# Glenn.net
KiCad netlist of a schematic drawn in Altium Designer
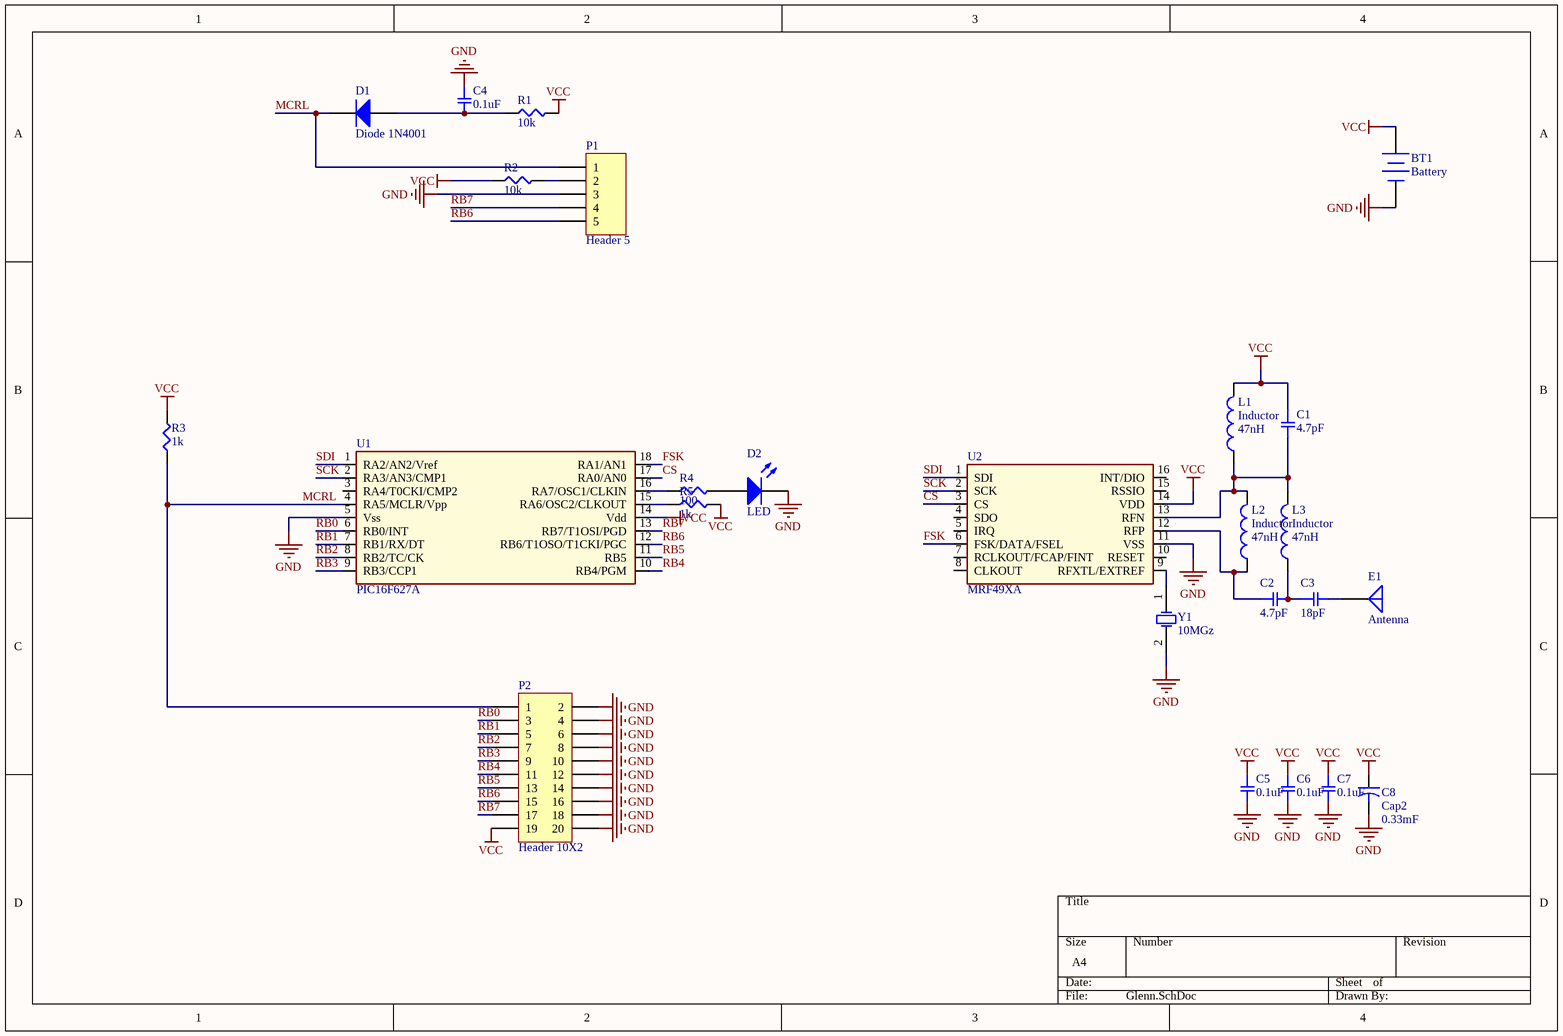
[diagram p0: Glenn.SchDoc]

(export (version "E")
  (design (tool "Eeschema 10.0.6"))
  (components
    (comp (ref "BT1")
      (value "Battery")
      (footprint "BAT-2")
      (description "Multicell Battery")
      (fields (field (name "PUBLISHER") "Altium Limited"))
      (libsource (lib "Miscellaneous Devices") (part "Battery"))
    )
    (comp (ref "C1")
      (value "4.7pF")
      (footprint "SMD-1206C")
      (description "CAP CER 0.033UF 250V X7T 1206")
      (fields
        (field (name "DIGI-KEY PART NUMBER") "490-13989-1-ND")
        (field (name "PART NUMBER") "GC331AD72E333KX01D")
      )
      (libsource (lib "capacitor_murata_1206") (part "GC331AD72E333KX01D"))
    )
    (comp (ref "C2")
      (value "4.7pF")
      (footprint "SMD-1206C")
      (description "CAP CER 0.033UF 250V X7T 1206")
      (fields
        (field (name "DIGI-KEY PART NUMBER") "490-13989-1-ND")
        (field (name "PART NUMBER") "GC331AD72E333KX01D")
      )
      (libsource (lib "capacitor_murata_1206") (part "GC331AD72E333KX01D"))
    )
    (comp (ref "C3")
      (value "18pF")
      (footprint "SMD-1206C")
      (description "CAP CER 0.033UF 250V X7T 1206")
      (fields
        (field (name "DIGI-KEY PART NUMBER") "490-13989-1-ND")
        (field (name "PART NUMBER") "GC331AD72E333KX01D")
      )
      (libsource (lib "capacitor_murata_1206") (part "GC331AD72E333KX01D"))
    )
    (comp (ref "C4")
      (value "0.1uF")
      (footprint "SMD-0805C")
      (description "CAP CER 10000PF 250V X7T 0805")
      (fields
        (field (name "DIGI-KEY PART NUMBER") "490-13986-1-ND")
        (field (name "PART NUMBER") "GC321AD72E103KX01D")
      )
      (libsource (lib "capacitor_murata_0805") (part "GC321AD72E103KX01D"))
    )
    (comp (ref "C5")
      (value "0.1uF")
      (footprint "SMD-0805C")
      (description "CAP CER 10000PF 250V X7T 0805")
      (fields
        (field (name "DIGI-KEY PART NUMBER") "490-13986-1-ND")
        (field (name "PART NUMBER") "GC321AD72E103KX01D")
      )
      (libsource (lib "capacitor_murata_0805") (part "GC321AD72E103KX01D"))
    )
    (comp (ref "C6")
      (value "0.1uF")
      (footprint "SMD-0805C")
      (description "CAP CER 10000PF 250V X7T 0805")
      (fields
        (field (name "DIGI-KEY PART NUMBER") "490-13986-1-ND")
        (field (name "PART NUMBER") "GC321AD72E103KX01D")
      )
      (libsource (lib "capacitor_murata_0805") (part "GC321AD72E103KX01D"))
    )
    (comp (ref "C7")
      (value "0.1uF")
      (footprint "SMD-0805C")
      (description "CAP CER 10000PF 250V X7T 0805")
      (fields
        (field (name "DIGI-KEY PART NUMBER") "490-13986-1-ND")
        (field (name "PART NUMBER") "GC321AD72E103KX01D")
      )
      (libsource (lib "capacitor_murata_0805") (part "GC321AD72E103KX01D"))
    )
    (comp (ref "C8")
      (value "Cap2")
      (footprint "CAPR5-4X5")
      (description "Capacitor")
      (fields (field (name "ALTIUM_VALUE") "0.33mF") (field (name "PUBLISHER") "Altium Limited"))
      (libsource (lib "Miscellaneous Devices") (part "Cap2"))
    )
    (comp (ref "D1")
      (value "Diode 1N4001")
      (footprint "DO-41")
      (description "1 Amp General Purpose Rectifier")
      (fields (field (name "PUBLISHER") "Altium Limited"))
      (libsource (lib "Miscellaneous Devices") (part "Diode 1N4001"))
    )
    (comp (ref "D2")
      (value "LED")
      (footprint "3.5X2.8X1.9")
      (description "Typical BLUE SiC LED")
      (fields (field (name "PUBLISHER") "Altium Limited"))
      (libsource (lib "Miscellaneous Devices") (part "LED3"))
    )
    (comp (ref "E1")
      (value "Antenna")
      (footprint "PIN1")
      (description "Generic Antenna")
      (fields (field (name "PUBLISHER") "Altium Limited"))
      (libsource (lib "Miscellaneous Devices") (part "Antenna"))
    )
    (comp (ref "L1")
      (value "Inductor")
      (footprint "0402-A")
      (fields (field (name "ALTIUM_VALUE") "47nH") (field (name "PUBLISHER") "Altium Limited"))
      (libsource (lib "Miscellaneous Devices") (part "Inductor"))
    )
    (comp (ref "L2")
      (value "Inductor")
      (footprint "0402-A")
      (fields (field (name "ALTIUM_VALUE") "47nH") (field (name "PUBLISHER") "Altium Limited"))
      (libsource (lib "Miscellaneous Devices") (part "Inductor"))
    )
    (comp (ref "L3")
      (value "Inductor")
      (footprint "0402-A")
      (fields (field (name "ALTIUM_VALUE") "47nH") (field (name "PUBLISHER") "Altium Limited"))
      (libsource (lib "Miscellaneous Devices") (part "Inductor"))
    )
    (comp (ref "P1")
      (value "Header 5")
      (footprint "HDR1X5")
      (description "Header, 5-Pin")
      (fields (field (name "PUBLISHER") "Altium Limited"))
      (libsource (lib "Miscellaneous Connectors") (part "Header 5"))
    )
    (comp (ref "P2")
      (value "Header 10X2")
      (footprint "HDR2X10")
      (description "Header, 10-Pin, Dual row")
      (fields (field (name "PUBLISHER") "Altium Limited"))
      (libsource (lib "Miscellaneous Connectors") (part "Header 10X2"))
    )
    (comp (ref "R1")
      (value "10k")
      (footprint "SMD-0805-RES")
      (description "RES SMD 1 OHM 1% 1/3W 0805")
      (fields (field (name "PART NUMBER") "ERJ-6BQF1R0V") (field (name "DIGI-KEY PART NUMBER") "P17499CT-ND"))
      (libsource (lib "Panasonic_ERJ_0805") (part "ERJ-6BQF1R0V"))
    )
    (comp (ref "R2")
      (value "10k")
      (footprint "SMD-0805-RES")
      (description "RES SMD 1 OHM 1% 1/3W 0805")
      (fields (field (name "PART NUMBER") "ERJ-6BQF1R0V") (field (name "DIGI-KEY PART NUMBER") "P17499CT-ND"))
      (libsource (lib "Panasonic_ERJ_0805") (part "ERJ-6BQF1R0V"))
    )
    (comp (ref "R3")
      (value "1k")
      (footprint "SMD-0805-RES")
      (description "RES SMD 1 OHM 1% 1/3W 0805")
      (fields (field (name "PART NUMBER") "ERJ-6BQF1R0V") (field (name "DIGI-KEY PART NUMBER") "P17499CT-ND"))
      (libsource (lib "Panasonic_ERJ_0805") (part "ERJ-6BQF1R0V"))
    )
    (comp (ref "R4")
      (value "100")
      (footprint "SMD-0805-RES")
      (description "RES SMD 1 OHM 1% 1/3W 0805")
      (fields (field (name "PART NUMBER") "ERJ-6BQF1R0V") (field (name "DIGI-KEY PART NUMBER") "P17499CT-ND"))
      (libsource (lib "Panasonic_ERJ_0805") (part "ERJ-6BQF1R0V"))
    )
    (comp (ref "R5")
      (value "1k")
      (footprint "SMD-0805-RES")
      (description "RES SMD 1 OHM 1% 1/3W 0805")
      (fields (field (name "PART NUMBER") "ERJ-6BQF1R0V") (field (name "DIGI-KEY PART NUMBER") "P17499CT-ND"))
      (libsource (lib "Panasonic_ERJ_0805") (part "ERJ-6BQF1R0V"))
    )
    (comp (ref "U1")
      (value "PIC16F627A")
      (footprint "RCU:PIC16F627A")
      (libsource (lib "RCU") (part "PIC16F627A"))
    )
    (comp (ref "U2") (value "MRF49XA") (footprint "RCU:MRF49XA") (libsource (lib "RCU") (part "MRF49XA")))
    (comp (ref "Y1")
      (value "10MGz")
      (footprint "R38")
      (description "Crystal Oscillator")
      (fields (field (name "PUBLISHER") "Altium Limited"))
      (libsource (lib "Miscellaneous Devices") (part "XTAL"))
    )
  )
  (nets
    (net (code "1") (name "/CS") (class "Default")
      (node (ref "U1") (pin "17") (pinfunction "RA0/AN0_17") (pintype "passive"))
      (node (ref "U2") (pin "3") (pinfunction "CS_3") (pintype "passive"))
    )
    (net (code "2") (name "/FSK") (class "Default")
      (node (ref "U1") (pin "18") (pinfunction "RA1/AN1_18") (pintype "passive"))
      (node (ref "U2") (pin "6") (pinfunction "FSK/DATA/FSEL_6") (pintype "passive"))
    )
    (net (code "3") (name "/MCRL") (class "Default")
      (node (ref "D1") (pin "2") (pinfunction "K_2") (pintype "passive"))
      (node (ref "P1") (pin "1") (pinfunction "1_1") (pintype "passive"))
      (node (ref "P2") (pin "1") (pinfunction "1_1") (pintype "passive"))
      (node (ref "R3") (pin "1") (pinfunction "1_1") (pintype "passive"))
      (node (ref "U1") (pin "4") (pinfunction "RA5/MCLR/Vpp_4") (pintype "passive"))
    )
    (net (code "4") (name "/RB0") (class "Default")
      (node (ref "P2") (pin "3") (pinfunction "3_3") (pintype "passive"))
      (node (ref "U1") (pin "6") (pinfunction "RB0/INT_6") (pintype "passive"))
    )
    (net (code "5") (name "/RB1") (class "Default")
      (node (ref "P2") (pin "5") (pinfunction "5_5") (pintype "passive"))
      (node (ref "U1") (pin "7") (pinfunction "RB1/RX/DT_7") (pintype "passive"))
    )
    (net (code "6") (name "/RB2") (class "Default")
      (node (ref "P2") (pin "7") (pinfunction "7_7") (pintype "passive"))
      (node (ref "U1") (pin "8") (pinfunction "RB2/TC/CK_8") (pintype "passive"))
    )
    (net (code "7") (name "/RB3") (class "Default")
      (node (ref "P2") (pin "9") (pinfunction "9_9") (pintype "passive"))
      (node (ref "U1") (pin "9") (pinfunction "RB3/CCP1_9") (pintype "passive"))
    )
    (net (code "8") (name "/RB4") (class "Default")
      (node (ref "P2") (pin "11") (pinfunction "11_11") (pintype "passive"))
      (node (ref "U1") (pin "10") (pinfunction "RB4/PGM_10") (pintype "passive"))
    )
    (net (code "9") (name "/RB5") (class "Default")
      (node (ref "P2") (pin "13") (pinfunction "13_13") (pintype "passive"))
      (node (ref "U1") (pin "11") (pinfunction "RB5_11") (pintype "passive"))
    )
    (net (code "10") (name "/RB6") (class "Default")
      (node (ref "P1") (pin "5") (pinfunction "5_5") (pintype "passive"))
      (node (ref "P2") (pin "15") (pinfunction "15_15") (pintype "passive"))
      (node (ref "U1") (pin "12") (pinfunction "RB6/T1OSO/T1CKI/PGC_12") (pintype "passive"))
    )
    (net (code "11") (name "/RB7") (class "Default")
      (node (ref "P1") (pin "4") (pinfunction "4_4") (pintype "passive"))
      (node (ref "P2") (pin "17") (pinfunction "17_17") (pintype "passive"))
      (node (ref "U1") (pin "13") (pinfunction "RB7/T1OSI/PGD_13") (pintype "passive"))
    )
    (net (code "12") (name "/SCK") (class "Default")
      (node (ref "U1") (pin "2") (pinfunction "RA3/AN3/CMP1_2") (pintype "passive"))
      (node (ref "U2") (pin "2") (pinfunction "SCK_2") (pintype "passive"))
    )
    (net (code "13") (name "/SDI") (class "Default")
      (node (ref "U1") (pin "1") (pinfunction "RA2/AN2/Vref_1") (pintype "passive"))
      (node (ref "U2") (pin "1") (pinfunction "SDI_1") (pintype "passive"))
    )
    (net (code "14") (name "GND") (class "Default")
      (node (ref "BT1") (pin "2") (pinfunction "-_2") (pintype "passive"))
      (node (ref "C4") (pin "1") (pinfunction "1_1") (pintype "passive"))
      (node (ref "C5") (pin "2") (pinfunction "2_2") (pintype "passive"))
      (node (ref "C6") (pin "2") (pinfunction "2_2") (pintype "passive"))
      (node (ref "C7") (pin "2") (pinfunction "2_2") (pintype "passive"))
      (node (ref "C8") (pin "2") (pinfunction "2_2") (pintype "passive"))
      (node (ref "D2") (pin "2") (pinfunction "K_2") (pintype "passive"))
      (node (ref "P1") (pin "3") (pinfunction "3_3") (pintype "passive"))
      (node (ref "P2") (pin "10") (pinfunction "10_10") (pintype "passive"))
      (node (ref "P2") (pin "12") (pinfunction "12_12") (pintype "passive"))
      (node (ref "P2") (pin "14") (pinfunction "14_14") (pintype "passive"))
      (node (ref "P2") (pin "16") (pinfunction "16_16") (pintype "passive"))
      (node (ref "P2") (pin "18") (pinfunction "18_18") (pintype "passive"))
      (node (ref "P2") (pin "2") (pinfunction "2_2") (pintype "passive"))
      (node (ref "P2") (pin "20") (pinfunction "20_20") (pintype "passive"))
      (node (ref "P2") (pin "4") (pinfunction "4_4") (pintype "passive"))
      (node (ref "P2") (pin "6") (pinfunction "6_6") (pintype "passive"))
      (node (ref "P2") (pin "8") (pinfunction "8_8") (pintype "passive"))
      (node (ref "U1") (pin "5") (pinfunction "Vss_5") (pintype "passive"))
      (node (ref "U2") (pin "11") (pinfunction "VSS_11") (pintype "passive"))
      (node (ref "Y1") (pin "2") (pinfunction "OSC2_2") (pintype "passive"))
    )
    (net (code "15") (name "Net-(C2-Pad2)") (class "Default")
      (node (ref "C2") (pin "2") (pinfunction "2_2") (pintype "passive"))
      (node (ref "C3") (pin "1") (pinfunction "1_1") (pintype "passive"))
      (node (ref "L3") (pin "1") (pinfunction "1_1") (pintype "passive"))
    )
    (net (code "16") (name "Net-(D1-A)") (class "Default")
      (node (ref "C4") (pin "2") (pinfunction "2_2") (pintype "passive"))
      (node (ref "D1") (pin "1") (pinfunction "A_1") (pintype "passive"))
      (node (ref "R1") (pin "1") (pinfunction "1_1") (pintype "passive"))
    )
    (net (code "17") (name "Net-(D2-A)") (class "Default")
      (node (ref "D2") (pin "1") (pinfunction "A_1") (pintype "passive"))
      (node (ref "R4") (pin "2") (pinfunction "2_2") (pintype "passive"))
    )
    (net (code "18") (name "Net-(E1-A)") (class "Default")
      (node (ref "C3") (pin "2") (pinfunction "2_2") (pintype "passive"))
      (node (ref "E1") (pin "1") (pinfunction "A_1") (pintype "passive"))
    )
    (net (code "19") (name "Net-(P1-Pad2)") (class "Default")
      (node (ref "P1") (pin "2") (pinfunction "2_2") (pintype "passive"))
      (node (ref "R2") (pin "2") (pinfunction "2_2") (pintype "passive"))
    )
    (net (code "20") (name "Net-(U1-RA6{slash}OSC2{slash}CLKOUT)") (class "Default")
      (node (ref "R5") (pin "1") (pinfunction "1_1") (pintype "passive"))
      (node (ref "U1") (pin "15") (pinfunction "RA6/OSC2/CLKOUT_15") (pintype "passive"))
    )
    (net (code "21") (name "Net-(U1-RA7{slash}OSC1{slash}CLKIN)") (class "Default")
      (node (ref "R4") (pin "1") (pinfunction "1_1") (pintype "passive"))
      (node (ref "U1") (pin "16") (pinfunction "RA7/OSC1/CLKIN_16") (pintype "passive"))
    )
    (net (code "22") (name "Net-(U2-RFN)") (class "Default")
      (node (ref "C1") (pin "2") (pinfunction "2_2") (pintype "passive"))
      (node (ref "L1") (pin "1") (pinfunction "1_1") (pintype "passive"))
      (node (ref "L2") (pin "2") (pinfunction "2_2") (pintype "passive"))
      (node (ref "L3") (pin "2") (pinfunction "2_2") (pintype "passive"))
      (node (ref "U2") (pin "13") (pinfunction "RFN_13") (pintype "passive"))
    )
    (net (code "23") (name "Net-(U2-RFP)") (class "Default")
      (node (ref "C2") (pin "1") (pinfunction "1_1") (pintype "passive"))
      (node (ref "L2") (pin "1") (pinfunction "1_1") (pintype "passive"))
      (node (ref "U2") (pin "12") (pinfunction "RFP_12") (pintype "passive"))
    )
    (net (code "24") (name "Net-(U2-RFXTL{slash}EXTREF)") (class "Default")
      (node (ref "U2") (pin "9") (pinfunction "RFXTL/EXTREF_9") (pintype "passive"))
      (node (ref "Y1") (pin "1") (pinfunction "OSC1_1") (pintype "passive"))
    )
    (net (code "25") (name "VCC") (class "Default")
      (node (ref "BT1") (pin "1") (pinfunction "+_1") (pintype "passive"))
      (node (ref "C1") (pin "1") (pinfunction "1_1") (pintype "passive"))
      (node (ref "C5") (pin "1") (pinfunction "1_1") (pintype "passive"))
      (node (ref "C6") (pin "1") (pinfunction "1_1") (pintype "passive"))
      (node (ref "C7") (pin "1") (pinfunction "1_1") (pintype "passive"))
      (node (ref "C8") (pin "1") (pinfunction "1_1") (pintype "passive"))
      (node (ref "L1") (pin "2") (pinfunction "2_2") (pintype "passive"))
      (node (ref "P2") (pin "19") (pinfunction "19_19") (pintype "passive"))
      (node (ref "R1") (pin "2") (pinfunction "2_2") (pintype "passive"))
      (node (ref "R2") (pin "1") (pinfunction "1_1") (pintype "passive"))
      (node (ref "R3") (pin "2") (pinfunction "2_2") (pintype "passive"))
      (node (ref "R5") (pin "2") (pinfunction "2_2") (pintype "passive"))
      (node (ref "U1") (pin "14") (pinfunction "Vdd_14") (pintype "passive"))
      (node (ref "U2") (pin "14") (pinfunction "VDD_14") (pintype "passive"))
    )
    (net (code "26") (name "unconnected-(U1-RA4{slash}T0CKI{slash}CMP2-Pad3)") (class "Default")
      (node (ref "U1") (pin "3") (pinfunction "RA4/T0CKI/CMP2_3") (pintype "passive"))
    )
    (net (code "27") (name "unconnected-(U2-CLKOUT-Pad8)") (class "Default")
      (node (ref "U2") (pin "8") (pinfunction "CLKOUT_8") (pintype "passive"))
    )
    (net (code "28") (name "unconnected-(U2-INT{slash}DIO-Pad16)") (class "Default")
      (node (ref "U2") (pin "16") (pinfunction "INT/DIO_16") (pintype "passive"))
    )
    (net (code "29") (name "unconnected-(U2-IRQ-Pad5)") (class "Default")
      (node (ref "U2") (pin "5") (pinfunction "IRQ_5") (pintype "passive"))
    )
    (net (code "30") (name "unconnected-(U2-RCLKOUT{slash}FCAP{slash}FINT-Pad7)") (class "Default")
      (node (ref "U2") (pin "7") (pinfunction "RCLKOUT/FCAP/FINT_7") (pintype "passive"))
    )
    (net (code "31") (name "unconnected-(U2-RESET-Pad10)") (class "Default")
      (node (ref "U2") (pin "10") (pinfunction "RESET_10") (pintype "passive"))
    )
    (net (code "32") (name "unconnected-(U2-RSSIO-Pad15)") (class "Default")
      (node (ref "U2") (pin "15") (pinfunction "RSSIO_15") (pintype "passive"))
    )
    (net (code "33") (name "unconnected-(U2-SDO-Pad4)") (class "Default")
      (node (ref "U2") (pin "4") (pinfunction "SDO_4") (pintype "passive"))
    )
  )
)
